# BreadBoard_Simple_Parallel_Resistive_Cir.net
KiCad netlist of a schematic drawn in EAGLE
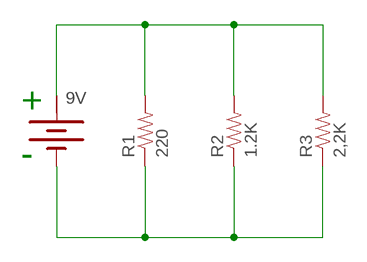
[diagram p0: schematic, sheet 1]

(export (version "E")
  (design (tool "Eeschema 10.0.6"))
  (components
    (comp (ref "BAT1")
      (value "9V")
      (footprint "eagle-import:BATTERY")
      (libsource (lib "eagle-import") (part "BATTERY"))
    )
    (comp (ref "R1")
      (value "220")
      (footprint "eagle-import:AXIAL-0.4")
      (libsource (lib "eagle-import") (part "RESISTORPTH-1/4W"))
    )
    (comp (ref "R2")
      (value "1.2K")
      (footprint "eagle-import:AXIAL-0.4")
      (libsource (lib "eagle-import") (part "RESISTORPTH-1/4W"))
    )
    (comp (ref "R3")
      (value "2,2K")
      (footprint "eagle-import:AXIAL-0.4")
      (libsource (lib "eagle-import") (part "RESISTORPTH-1/4W"))
    )
  )
  (nets
    (net (code "1") (name "/+") (class "Default")
      (node (ref "BAT1") (pin "+@1") (pinfunction "+_+@1") (pintype "power_in"))
    )
    (net (code "2") (name "Net-(R1-1)") (class "Default")
      (node (ref "BAT1") (pin "-") (pinfunction "-_-") (pintype "power_in"))
      (node (ref "R1") (pin "P$1") (pinfunction "1_P$1") (pintype "passive"))
      (node (ref "R2") (pin "P$1") (pinfunction "1_P$1") (pintype "passive"))
      (node (ref "R3") (pin "P$1") (pinfunction "1_P$1") (pintype "passive"))
    )
    (net (code "3") (name "Net-(R1-2)") (class "Default")
      (node (ref "BAT1") (pin "+") (pinfunction "+_+") (pintype "power_in"))
      (node (ref "R1") (pin "P$2") (pinfunction "2_P$2") (pintype "passive"))
      (node (ref "R2") (pin "P$2") (pinfunction "2_P$2") (pintype "passive"))
      (node (ref "R3") (pin "P$2") (pinfunction "2_P$2") (pintype "passive"))
    )
  )
)
